# openmv4.net
KiCad netlist of a schematic drawn in Altium Designer
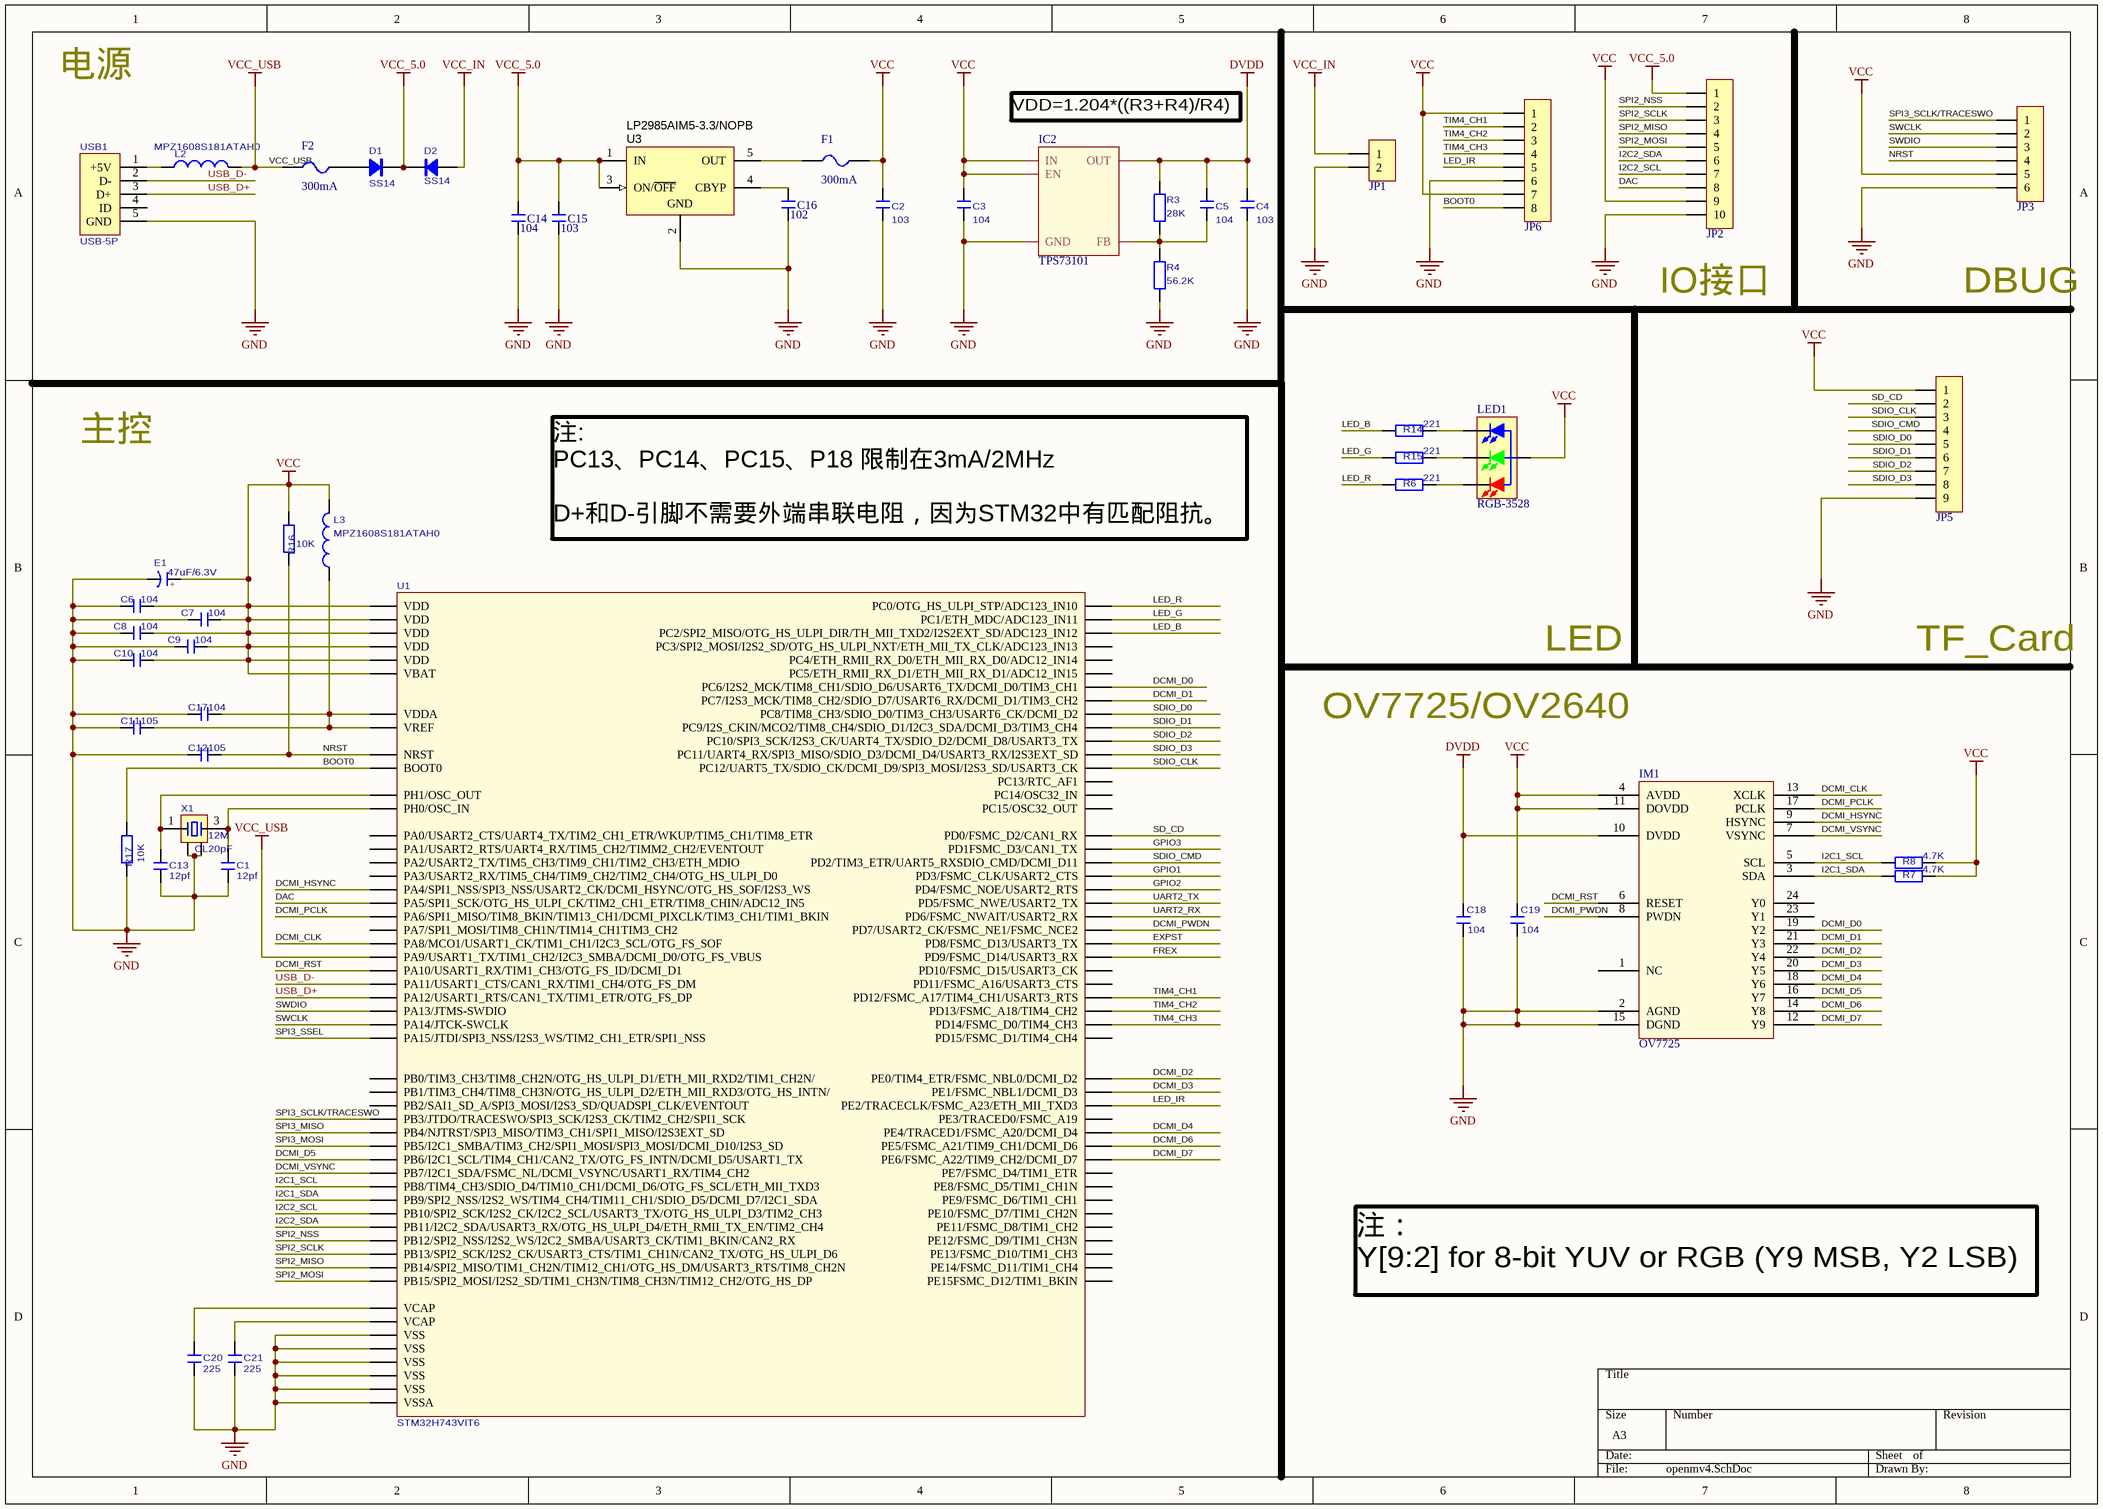
[diagram p0: openmv4.SchDoc]

(export (version "E")
  (design (tool "Eeschema 10.0.6"))
  (components
    (comp (ref "C1")
      (value "12pf")
      (footprint "C 0603_M")
      (description "无极性贴片电容")
      (fields (field (name "版权归属") "源创客"))
      (libsource (lib "3.1   - 电阻-电容-电感") (part "C"))
    )
    (comp (ref "C2")
      (value "103")
      (footprint "C 0603_M")
      (description "无极性贴片电容")
      (fields (field (name "版权归属") "源创客"))
      (libsource (lib "3.1   - 电阻-电容-电感") (part "C"))
    )
    (comp (ref "C3")
      (value "104")
      (footprint "C 0603_M")
      (description "无极性贴片电容")
      (fields (field (name "版权归属") "源创客"))
      (libsource (lib "3.1   - 电阻-电容-电感") (part "C"))
    )
    (comp (ref "C4")
      (value "103")
      (footprint "C 0603_M")
      (description "无极性贴片电容")
      (fields (field (name "版权归属") "源创客"))
      (libsource (lib "3.1   - 电阻-电容-电感") (part "C"))
    )
    (comp (ref "C5")
      (value "104")
      (footprint "C 0603_M")
      (description "无极性贴片电容")
      (fields (field (name "版权归属") "源创客"))
      (libsource (lib "3.1   - 电阻-电容-电感") (part "C"))
    )
    (comp (ref "C6")
      (value "104")
      (footprint "C 0603_M")
      (description "无极性贴片电容")
      (fields (field (name "版权归属") "源创客"))
      (libsource (lib "3.1   - 电阻-电容-电感") (part "C"))
    )
    (comp (ref "C7")
      (value "104")
      (footprint "C 0603_M")
      (description "无极性贴片电容")
      (fields (field (name "版权归属") "源创客"))
      (libsource (lib "3.1   - 电阻-电容-电感") (part "C"))
    )
    (comp (ref "C8")
      (value "104")
      (footprint "C 0603_M")
      (description "无极性贴片电容")
      (fields (field (name "版权归属") "源创客"))
      (libsource (lib "3.1   - 电阻-电容-电感") (part "C"))
    )
    (comp (ref "C9")
      (value "104")
      (footprint "C 0603_M")
      (description "无极性贴片电容")
      (fields (field (name "版权归属") "源创客"))
      (libsource (lib "3.1   - 电阻-电容-电感") (part "C"))
    )
    (comp (ref "C10")
      (value "104")
      (footprint "C 0603_M")
      (description "无极性贴片电容")
      (fields (field (name "版权归属") "源创客"))
      (libsource (lib "3.1   - 电阻-电容-电感") (part "C"))
    )
    (comp (ref "C11")
      (value "105")
      (footprint "C 0603_M")
      (description "无极性贴片电容")
      (fields (field (name "版权归属") "源创客"))
      (libsource (lib "3.1   - 电阻-电容-电感") (part "C"))
    )
    (comp (ref "C12")
      (value "105")
      (footprint "C 0603_M")
      (description "无极性贴片电容")
      (fields (field (name "版权归属") "源创客"))
      (libsource (lib "3.1   - 电阻-电容-电感") (part "C"))
    )
    (comp (ref "C13")
      (value "12pf")
      (footprint "C 0603_M")
      (description "无极性贴片电容")
      (fields (field (name "版权归属") "源创客"))
      (libsource (lib "3.1   - 电阻-电容-电感") (part "C"))
    )
    (comp (ref "C14")
      (value "104")
      (footprint "C 0603_M")
      (description "无极性贴片电容")
      (fields (field (name "版权归属") "源创客"))
      (libsource (lib "3.1   - 电阻-电容-电感") (part "C"))
    )
    (comp (ref "C15")
      (value "103")
      (footprint "C 0603_M")
      (description "无极性贴片电容")
      (fields (field (name "版权归属") "源创客"))
      (libsource (lib "3.1   - 电阻-电容-电感") (part "C"))
    )
    (comp (ref "C16")
      (value "102")
      (footprint "C 0603_M")
      (description "无极性贴片电容")
      (fields (field (name "版权归属") "源创客"))
      (libsource (lib "3.1   - 电阻-电容-电感") (part "C"))
    )
    (comp (ref "C17")
      (value "104")
      (footprint "C 0603_M")
      (description "无极性贴片电容")
      (fields (field (name "版权归属") "源创客"))
      (libsource (lib "3.1   - 电阻-电容-电感") (part "C"))
    )
    (comp (ref "C18")
      (value "104")
      (footprint "C 0603_M")
      (description "无极性贴片电容")
      (fields (field (name "版权归属") "源创客"))
      (libsource (lib "3.1   - 电阻-电容-电感") (part "C"))
    )
    (comp (ref "C19")
      (value "104")
      (footprint "C 0603_M")
      (description "无极性贴片电容")
      (fields (field (name "版权归属") "源创客"))
      (libsource (lib "3.1   - 电阻-电容-电感") (part "C"))
    )
    (comp (ref "C20")
      (value "225")
      (footprint "C 0603_M")
      (description "无极性贴片电容")
      (fields (field (name "版权归属") "源创客"))
      (libsource (lib "3.1   - 电阻-电容-电感") (part "C"))
    )
    (comp (ref "C21")
      (value "225")
      (footprint "C 0603_M")
      (description "无极性贴片电容")
      (fields (field (name "版权归属") "源创客"))
      (libsource (lib "3.1   - 电阻-电容-电感") (part "C"))
    )
    (comp (ref "D1")
      (value "SS14")
      (footprint "SOD-323")
      (description "肖特基二极管")
      (fields (field (name "版权归属") "源创客"))
      (libsource (lib "8.1   - 二极管-整流桥") (part "SS14"))
    )
    (comp (ref "D2")
      (value "SS14")
      (footprint "SOD-323")
      (description "肖特基二极管")
      (fields (field (name "版权归属") "源创客"))
      (libsource (lib "8.1   - 二极管-整流桥") (part "SS14"))
    )
    (comp (ref "E1")
      (value "47uF/6.3V")
      (footprint "CD A(3216)")
      (description "贴片钽电容")
      (fields (field (name "版权归属") "源创客"))
      (libsource (lib "3.1   - 电阻-电容-电感") (part "C-CD"))
    )
    (comp (ref "F1")
      (value "300mA")
      (footprint "FU 0805")
      (description "贴片保险丝")
      (fields (field (name "版权归属") "源创客"))
      (libsource (lib "10.1 - 保险丝-晶振") (part "FU"))
    )
    (comp (ref "F2")
      (value "300mA")
      (footprint "FU 0603")
      (description "贴片保险丝")
      (fields (field (name "版权归属") "源创客"))
      (libsource (lib "10.1 - 保险丝-晶振") (part "FU"))
    )
    (comp (ref "IC2") (value "TPS73101") (footprint "SOT23-5M") (libsource (lib "TPS731") (part "TPS731")))
    (comp (ref "IM1")
      (value "OV7725")
      (footprint "FPC0.5 2H-WS-24P")
      (libsource (lib "OV7725-Down") (part "OV7725_Down"))
    )
    (comp (ref "JP1")
      (value "HDR-1X2")
      (footprint "MX 1.25-WS-2P")
      (description "2P接插件")
      (fields (field (name "版权归属") "源创客"))
      (libsource (lib "4.2   - 接插件-脚距1.25") (part "Header 2"))
    )
    (comp (ref "JP2")
      (value "HDR-1X10")
      (footprint "MX 1.25-WS-10P")
      (description "10P接插件")
      (fields (field (name "版权归属") "源创客"))
      (libsource (lib "4.2   - 接插件-脚距1.25") (part "Header 10"))
    )
    (comp (ref "JP3")
      (value "HDR-1X6")
      (footprint "MX 1.25-WS-6P")
      (description "6P接插件")
      (fields (field (name "版权归属") "源创客"))
      (libsource (lib "4.2   - 接插件-脚距1.25") (part "Header 6"))
    )
    (comp (ref "JP5")
      (value "FPC1.0-9P")
      (footprint "FPC0.5 2H-WS-9P")
      (description "FPC连接器")
      (fields (field (name "版权归属") "源创客"))
      (libsource (lib "4.15 - FPC连接器") (part "FPC-9P"))
    )
    (comp (ref "JP6")
      (value "HDR-1X8")
      (footprint "MX 1.25-WS-8P")
      (description "8P接插件")
      (fields (field (name "版权归属") "源创客"))
      (libsource (lib "4.2   - 接插件-脚距1.25") (part "Header 8"))
    )
    (comp (ref "L2")
      (value "MPZ1608S181ATAH0")
      (footprint "L 0603_M")
      (description "小功率贴片电感")
      (fields (field (name "版权归属") "源创客"))
      (libsource (lib "3.1   - 电阻-电容-电感") (part "L"))
    )
    (comp (ref "L3")
      (value "MPZ1608S181ATAH0")
      (footprint "L 0603_M")
      (description "小功率贴片电感")
      (fields (field (name "版权归属") "源创客"))
      (libsource (lib "3.1   - 电阻-电容-电感") (part "L"))
    )
    (comp (ref "LED1")
      (value "RGB-3528")
      (footprint "LED 3528-4Pin")
      (description "三基色LED")
      (fields (field (name "版权归属") "源创客"))
      (libsource (lib "9.1   - LED") (part "LED-RGB-3528"))
    )
    (comp (ref "R3")
      (value "28K")
      (footprint "R 0603_M")
      (description "贴片电阻")
      (fields (field (name "版权归属") "源创客"))
      (libsource (lib "3.1   - 电阻-电容-电感") (part "R"))
    )
    (comp (ref "R4")
      (value "56.2K")
      (footprint "R 0603_M")
      (description "贴片电阻")
      (fields (field (name "版权归属") "源创客"))
      (libsource (lib "3.1   - 电阻-电容-电感") (part "R"))
    )
    (comp (ref "R6")
      (value "221")
      (footprint "R 0603_M")
      (description "贴片电阻")
      (fields (field (name "版权归属") "源创客"))
      (libsource (lib "3.1   - 电阻-电容-电感") (part "R"))
    )
    (comp (ref "R7")
      (value "4.7K")
      (description "贴片电阻")
      (fields (field (name "版权归属") "源创客"))
      (libsource (lib "3.1   - 电阻-电容-电感") (part "R"))
    )
    (comp (ref "R8")
      (value "4.7K")
      (description "贴片电阻")
      (fields (field (name "版权归属") "源创客"))
      (libsource (lib "3.1   - 电阻-电容-电感") (part "R"))
    )
    (comp (ref "R14")
      (value "221")
      (footprint "R 0603_M")
      (description "贴片电阻")
      (fields (field (name "版权归属") "源创客"))
      (libsource (lib "3.1   - 电阻-电容-电感") (part "R"))
    )
    (comp (ref "R15")
      (value "221")
      (footprint "R 0603_M")
      (description "贴片电阻")
      (fields (field (name "版权归属") "源创客"))
      (libsource (lib "3.1   - 电阻-电容-电感") (part "R"))
    )
    (comp (ref "R16")
      (value "10K")
      (footprint "R 0603_M")
      (description "贴片电阻")
      (fields (field (name "版权归属") "源创客"))
      (libsource (lib "3.1   - 电阻-电容-电感") (part "R"))
    )
    (comp (ref "R17")
      (value "10K")
      (footprint "R 0603_M")
      (description "贴片电阻")
      (fields (field (name "版权归属") "源创客"))
      (libsource (lib "3.1   - 电阻-电容-电感") (part "R"))
    )
    (comp (ref "U1")
      (value "STM32H743VIT6")
      (footprint "LQFP100 14x14_M")
      (libsource (lib "STM32H743VIT6") (part "STM32H743VIT6"))
    )
    (comp (ref "U3")
      (value "LP2985AIM5-3.3/NOPB")
      (footprint "SOT23-5L")
      (description "Micropower 150 mA Low-Noise Ultra Low-Dropout Regulator, 5-pin SOT-23, Pb-Free")
      (fields (field (name "MANUFACTURER") "Texas Instruments") (field (name "PUBLISHER") "Altium Limited"))
      (libsource (lib "NSC LDO") (part "LP2985AIM5-3.3/NOPB"))
    )
    (comp (ref "USB1")
      (value "USB-5P")
      (footprint "USB-MICRO_A")
      (description "微型USB母座")
      (fields (field (name "版权归属") "源创客"))
      (libsource (lib "4.1   - 接口类") (part "USB-5P"))
    )
    (comp (ref "X1")
      (value "12M")
      (footprint "OSC 2025-4P")
      (description "4脚无源晶振")
      (fields (field (name "负载电容") "CL20pF") (field (name "版权归属") "源创客"))
      (libsource (lib "10.1 - 保险丝-晶振") (part "XTAL-4P"))
    )
  )
  (nets
    (net (code "1") (name "/BOOT0") (class "Default")
      (node (ref "JP6") (pin "8") (pinfunction "8_8") (pintype "passive"))
      (node (ref "R17") (pin "2") (pinfunction "2_2") (pintype "passive"))
      (node (ref "U1") (pin "94") (pinfunction "BOOT0_94") (pintype "passive"))
    )
    (net (code "2") (name "/DAC") (class "Default")
      (node (ref "JP2") (pin "8") (pinfunction "8_8") (pintype "passive"))
      (node (ref "U1") (pin "29") (pinfunction "PA5/SPI1_SCK/OTG_HS_ULPI_CK/TIM2_CH1_ETR/TIM8_CHIN/ADC12_IN5_29") (pintype "passive"))
    )
    (net (code "3") (name "/DCMI_CLK") (class "Default")
      (node (ref "IM1") (pin "13") (pinfunction "XCLK_13") (pintype "power_in"))
      (node (ref "U1") (pin "67") (pinfunction "PA8/MCO1/USART1_CK/TIM1_CH1/I2C3_SCL/OTG_FS_SOF_67") (pintype "passive"))
    )
    (net (code "4") (name "/DCMI_D0") (class "Default")
      (node (ref "IM1") (pin "19") (pinfunction "Y2_19") (pintype "power_in"))
      (node (ref "U1") (pin "63") (pinfunction "PC6/I2S2_MCK/TIM8_CH1/SDIO_D6/USART6_TX/DCMI_D0/TIM3_CH1_63") (pintype "passive"))
    )
    (net (code "5") (name "/DCMI_D1") (class "Default")
      (node (ref "IM1") (pin "21") (pinfunction "Y3_21") (pintype "power_in"))
      (node (ref "U1") (pin "64") (pinfunction "PC7/I2S3_MCK/TIM8_CH2/SDIO_D7/USART6_RX/DCMI_D1/TIM3_CH2_64") (pintype "passive"))
    )
    (net (code "6") (name "/DCMI_D2") (class "Default")
      (node (ref "IM1") (pin "22") (pinfunction "Y4_22") (pintype "power_in"))
      (node (ref "U1") (pin "97") (pinfunction "PE0/TIM4_ETR/FSMC_NBL0/DCMI_D2_97") (pintype "passive"))
    )
    (net (code "7") (name "/DCMI_D3") (class "Default")
      (node (ref "IM1") (pin "20") (pinfunction "Y5_20") (pintype "power_in"))
      (node (ref "U1") (pin "98") (pinfunction "PE1/FSMC_NBL1/DCMI_D3_98") (pintype "passive"))
    )
    (net (code "8") (name "/DCMI_D4") (class "Default")
      (node (ref "IM1") (pin "18") (pinfunction "Y6_18") (pintype "power_in"))
      (node (ref "U1") (pin "3") (pinfunction "PE4/TRACED1/FSMC_A20/DCMI_D4_3") (pintype "passive"))
    )
    (net (code "9") (name "/DCMI_D5") (class "Default")
      (node (ref "IM1") (pin "16") (pinfunction "Y7_16") (pintype "power_in"))
      (node (ref "U1") (pin "92") (pinfunction "PB6/I2C1_SCL/TIM4_CH1/CAN2_TX/OTG_FS_INTN/DCMI_D5/USART1_TX_92") (pintype "passive"))
    )
    (net (code "10") (name "/DCMI_D6") (class "Default")
      (node (ref "IM1") (pin "14") (pinfunction "Y8_14") (pintype "power_in"))
      (node (ref "U1") (pin "4") (pinfunction "PE5/FSMC_A21/TIM9_CH1/DCMI_D6_4") (pintype "passive"))
    )
    (net (code "11") (name "/DCMI_D7") (class "Default")
      (node (ref "IM1") (pin "12") (pinfunction "Y9_12") (pintype "power_in"))
      (node (ref "U1") (pin "5") (pinfunction "PE6/FSMC_A22/TIM9_CH2/DCMI_D7_5") (pintype "passive"))
    )
    (net (code "12") (name "/DCMI_HSYNC") (class "Default")
      (node (ref "IM1") (pin "9") (pinfunction "HSYNC_9") (pintype "power_in"))
      (node (ref "U1") (pin "28") (pinfunction "PA4/SPI1_NSS/SPI3_NSS/USART2_CK/DCMI_HSYNC/OTG_HS_SOF/I2S3_WS_28") (pintype "passive"))
    )
    (net (code "13") (name "/DCMI_PCLK") (class "Default")
      (node (ref "IM1") (pin "17") (pinfunction "PCLK_17") (pintype "power_in"))
      (node (ref "U1") (pin "30") (pinfunction "PA6/SPI1_MISO/TIM8_BKIN/TIM13_CH1/DCMI_PIXCLK/TIM3_CH1/TIM1_BKIN_30") (pintype "passive"))
    )
    (net (code "14") (name "/DCMI_PWDN") (class "Default")
      (node (ref "IM1") (pin "8") (pinfunction "PWDN_8") (pintype "power_in"))
      (node (ref "U1") (pin "88") (pinfunction "PD7/USART2_CK/FSMC_NE1/FSMC_NCE2_88") (pintype "passive"))
    )
    (net (code "15") (name "/DCMI_RST") (class "Default")
      (node (ref "IM1") (pin "6") (pinfunction "RESET_6") (pintype "power_in"))
      (node (ref "U1") (pin "69") (pinfunction "PA10/USART1_RX/TIM1_CH3/OTG_FS_ID/DCMI_D1_69") (pintype "passive"))
    )
    (net (code "16") (name "/DCMI_VSYNC") (class "Default")
      (node (ref "IM1") (pin "7") (pinfunction "VSYNC_7") (pintype "power_in"))
      (node (ref "U1") (pin "93") (pinfunction "PB7/I2C1_SDA/FSMC_NL/DCMI_VSYNC/USART1_RX/TIM4_CH2_93") (pintype "passive"))
    )
    (net (code "17") (name "/EXPST") (class "Default")
      (node (ref "U1") (pin "55") (pinfunction "PD8/FSMC_D13/USART3_TX_55") (pintype "passive"))
    )
    (net (code "18") (name "/FREX") (class "Default")
      (node (ref "U1") (pin "56") (pinfunction "PD9/FSMC_D14/USART3_RX_56") (pintype "passive"))
    )
    (net (code "19") (name "/GPIO1") (class "Default")
      (node (ref "U1") (pin "84") (pinfunction "PD3/FSMC_CLK/USART2_CTS_84") (pintype "passive"))
    )
    (net (code "20") (name "/GPIO2") (class "Default")
      (node (ref "U1") (pin "85") (pinfunction "PD4/FSMC_NOE/USART2_RTS_85") (pintype "passive"))
    )
    (net (code "21") (name "/GPIO3") (class "Default")
      (node (ref "U1") (pin "82") (pinfunction "PD1FSMC_D3/CAN1_TX_82") (pintype "passive"))
    )
    (net (code "22") (name "/I2C1_SCL") (class "Default")
      (node (ref "IM1") (pin "5") (pinfunction "SCL_5") (pintype "power_in"))
      (node (ref "R8") (pin "2") (pinfunction "2_2") (pintype "passive"))
      (node (ref "U1") (pin "95") (pinfunction "PB8/TIM4_CH3/SDIO_D4/TIM10_CH1/DCMI_D6/OTG_FS_SCL/ETH_MII_TXD3_95") (pintype "passive"))
    )
    (net (code "23") (name "/I2C1_SDA") (class "Default")
      (node (ref "IM1") (pin "3") (pinfunction "SDA_3") (pintype "power_in"))
      (node (ref "R7") (pin "2") (pinfunction "2_2") (pintype "passive"))
      (node (ref "U1") (pin "96") (pinfunction "PB9/SPI2_NSS/I2S2_WS/TIM4_CH4/TIM11_CH1/SDIO_D5/DCMI_D7/I2C1_SDA_96") (pintype "passive"))
    )
    (net (code "24") (name "/I2C2_SCL") (class "Default")
      (node (ref "JP2") (pin "7") (pinfunction "7_7") (pintype "passive"))
      (node (ref "U1") (pin "46") (pinfunction "PB10/SPI2_SCK/I2S2_CK/I2C2_SCL/USART3_TX/OTG_HS_ULPI_D3/TIM2_CH3_46") (pintype "passive"))
    )
    (net (code "25") (name "/I2C2_SDA") (class "Default")
      (node (ref "JP2") (pin "6") (pinfunction "6_6") (pintype "passive"))
      (node (ref "U1") (pin "47") (pinfunction "PB11/I2C2_SDA/USART3_RX/OTG_HS_ULPI_D4/ETH_RMII_TX_EN/TIM2_CH4_47") (pintype "passive"))
    )
    (net (code "26") (name "/LED_B") (class "Default")
      (node (ref "R14") (pin "2") (pinfunction "2_2") (pintype "passive"))
      (node (ref "U1") (pin "17") (pinfunction "PC2/SPI2_MISO/OTG_HS_ULPI_DIR/TH_MII_TXD2/I2S2EXT_SD/ADC123_IN12_17") (pintype "passive"))
    )
    (net (code "27") (name "/LED_G") (class "Default")
      (node (ref "R15") (pin "2") (pinfunction "2_2") (pintype "passive"))
      (node (ref "U1") (pin "16") (pinfunction "PC1/ETH_MDC/ADC123_IN11_16") (pintype "passive"))
    )
    (net (code "28") (name "/LED_IR") (class "Default")
      (node (ref "JP6") (pin "5") (pinfunction "5_5") (pintype "passive"))
      (node (ref "U1") (pin "1") (pinfunction "PE2/TRACECLK/FSMC_A23/ETH_MII_TXD3_1") (pintype "passive"))
    )
    (net (code "29") (name "/LED_R") (class "Default")
      (node (ref "R6") (pin "2") (pinfunction "2_2") (pintype "passive"))
      (node (ref "U1") (pin "15") (pinfunction "PC0/OTG_HS_ULPI_STP/ADC123_IN10_15") (pintype "passive"))
    )
    (net (code "30") (name "/NRST") (class "Default")
      (node (ref "C12") (pin "1") (pinfunction "1_1") (pintype "passive"))
      (node (ref "JP3") (pin "4") (pinfunction "4_4") (pintype "passive"))
      (node (ref "R16") (pin "1") (pinfunction "1_1") (pintype "passive"))
      (node (ref "U1") (pin "14") (pinfunction "NRST_14") (pintype "passive"))
    )
    (net (code "31") (name "/SDIO_CLK") (class "Default")
      (node (ref "JP5") (pin "3") (pinfunction "3_3") (pintype "passive"))
      (node (ref "U1") (pin "80") (pinfunction "PC12/UART5_TX/SDIO_CK/DCMI_D9/SPI3_MOSI/I2S3_SD/USART3_CK_80") (pintype "passive"))
    )
    (net (code "32") (name "/SDIO_CMD") (class "Default")
      (node (ref "JP5") (pin "4") (pinfunction "4_4") (pintype "passive"))
      (node (ref "U1") (pin "83") (pinfunction "PD2/TIM3_ETR/UART5_RXSDIO_CMD/DCMI_D11_83") (pintype "passive"))
    )
    (net (code "33") (name "/SDIO_D0") (class "Default")
      (node (ref "JP5") (pin "5") (pinfunction "5_5") (pintype "passive"))
      (node (ref "U1") (pin "65") (pinfunction "PC8/TIM8_CH3/SDIO_D0/TIM3_CH3/USART6_CK/DCMI_D2_65") (pintype "passive"))
    )
    (net (code "34") (name "/SDIO_D1") (class "Default")
      (node (ref "JP5") (pin "6") (pinfunction "6_6") (pintype "passive"))
      (node (ref "U1") (pin "66") (pinfunction "PC9/I2S_CKIN/MCO2/TIM8_CH4/SDIO_D1/I2C3_SDA/DCMI_D3/TIM3_CH4_66") (pintype "passive"))
    )
    (net (code "35") (name "/SDIO_D2") (class "Default")
      (node (ref "JP5") (pin "7") (pinfunction "7_7") (pintype "passive"))
      (node (ref "U1") (pin "78") (pinfunction "PC10/SPI3_SCK/I2S3_CK/UART4_TX/SDIO_D2/DCMI_D8/USART3_TX_78") (pintype "passive"))
    )
    (net (code "36") (name "/SDIO_D3") (class "Default")
      (node (ref "JP5") (pin "8") (pinfunction "8_8") (pintype "passive"))
      (node (ref "U1") (pin "79") (pinfunction "PC11/UART4_RX/SPI3_MISO/SDIO_D3/DCMI_D4/USART3_RX/I2S3EXT_SD_79") (pintype "passive"))
    )
    (net (code "37") (name "/SD_CD") (class "Default")
      (node (ref "JP5") (pin "2") (pinfunction "2_2") (pintype "passive"))
      (node (ref "U1") (pin "81") (pinfunction "PD0/FSMC_D2/CAN1_RX_81") (pintype "passive"))
    )
    (net (code "38") (name "/SPI2_MISO") (class "Default")
      (node (ref "JP2") (pin "4") (pinfunction "4_4") (pintype "passive"))
      (node (ref "U1") (pin "53") (pinfunction "PB14/SPI2_MISO/TIM1_CH2N/TIM12_CH1/OTG_HS_DM/USART3_RTS/TIM8_CH2N_53") (pintype "passive"))
    )
    (net (code "39") (name "/SPI2_MOSI") (class "Default")
      (node (ref "JP2") (pin "5") (pinfunction "5_5") (pintype "passive"))
      (node (ref "U1") (pin "54") (pinfunction "PB15/SPI2_MOSI/I2S2_SD/TIM1_CH3N/TIM8_CH3N/TIM12_CH2/OTG_HS_DP_54") (pintype "passive"))
    )
    (net (code "40") (name "/SPI2_NSS") (class "Default")
      (node (ref "JP2") (pin "2") (pinfunction "2_2") (pintype "passive"))
      (node (ref "U1") (pin "51") (pinfunction "PB12/SPI2_NSS/I2S2_WS/I2C2_SMBA/USART3_CK/TIM1_BKIN/CAN2_RX_51") (pintype "passive"))
    )
    (net (code "41") (name "/SPI2_SCLK") (class "Default")
      (node (ref "JP2") (pin "3") (pinfunction "3_3") (pintype "passive"))
      (node (ref "U1") (pin "52") (pinfunction "PB13/SPI2_SCK/I2S2_CK/USART3_CTS/TIM1_CH1N/CAN2_TX/OTG_HS_ULPI_D6_52") (pintype "passive"))
    )
    (net (code "42") (name "/SPI3_MISO") (class "Default")
      (node (ref "U1") (pin "90") (pinfunction "PB4/NJTRST/SPI3_MISO/TIM3_CH1/SPI1_MISO/I2S3EXT_SD_90") (pintype "passive"))
    )
    (net (code "43") (name "/SPI3_MOSI") (class "Default")
      (node (ref "U1") (pin "91") (pinfunction "PB5/I2C1_SMBA/TIM3_CH2/SPI1_MOSI/SPI3_MOSI/DCMI_D10/I2S3_SD_91") (pintype "passive"))
    )
    (net (code "44") (name "/SPI3_SCLK{slash}TRACESWO") (class "Default")
      (node (ref "JP3") (pin "1") (pinfunction "1_1") (pintype "passive"))
      (node (ref "U1") (pin "89") (pinfunction "PB3/JTDO/TRACESWO/SPI3_SCK/I2S3_CK/TIM2_CH2/SPI1_SCK_89") (pintype "passive"))
    )
    (net (code "45") (name "/SPI3_SSEL") (class "Default")
      (node (ref "U1") (pin "77") (pinfunction "PA15/JTDI/SPI3_NSS/I2S3_WS/TIM2_CH1_ETR/SPI1_NSS_77") (pintype "passive"))
    )
    (net (code "46") (name "/SWCLK") (class "Default")
      (node (ref "JP3") (pin "2") (pinfunction "2_2") (pintype "passive"))
      (node (ref "U1") (pin "76") (pinfunction "PA14/JTCK-SWCLK_76") (pintype "passive"))
    )
    (net (code "47") (name "/SWDIO") (class "Default")
      (node (ref "JP3") (pin "3") (pinfunction "3_3") (pintype "passive"))
      (node (ref "U1") (pin "72") (pinfunction "PA13/JTMS-SWDIO_72") (pintype "passive"))
    )
    (net (code "48") (name "/TIM4_CH1") (class "Default")
      (node (ref "JP6") (pin "2") (pinfunction "2_2") (pintype "passive"))
      (node (ref "U1") (pin "59") (pinfunction "PD12/FSMC_A17/TIM4_CH1/USART3_RTS_59") (pintype "passive"))
    )
    (net (code "49") (name "/TIM4_CH2") (class "Default")
      (node (ref "JP6") (pin "3") (pinfunction "3_3") (pintype "passive"))
      (node (ref "U1") (pin "60") (pinfunction "PD13/FSMC_A18/TIM4_CH2_60") (pintype "passive"))
    )
    (net (code "50") (name "/TIM4_CH3") (class "Default")
      (node (ref "JP6") (pin "4") (pinfunction "4_4") (pintype "passive"))
      (node (ref "U1") (pin "61") (pinfunction "PD14/FSMC_D0/TIM4_CH3_61") (pintype "passive"))
    )
    (net (code "51") (name "/UART2_RX") (class "Default")
      (node (ref "U1") (pin "87") (pinfunction "PD6/FSMC_NWAIT/USART2_RX_87") (pintype "passive"))
    )
    (net (code "52") (name "/UART2_TX") (class "Default")
      (node (ref "U1") (pin "86") (pinfunction "PD5/FSMC_NWE/USART2_TX_86") (pintype "passive"))
    )
    (net (code "53") (name "/USB_D+") (class "Default")
      (node (ref "U1") (pin "71") (pinfunction "PA12/USART1_RTS/CAN1_TX/TIM1_ETR/OTG_FS_DP_71") (pintype "passive"))
      (node (ref "USB1") (pin "3") (pinfunction "D+_3") (pintype "passive"))
    )
    (net (code "54") (name "/USB_D-") (class "Default")
      (node (ref "U1") (pin "70") (pinfunction "PA11/USART1_CTS/CAN1_RX/TIM1_CH4/OTG_FS_DM_70") (pintype "passive"))
      (node (ref "USB1") (pin "2") (pinfunction "D-_2") (pintype "passive"))
    )
    (net (code "55") (name "DVDD") (class "Default")
      (node (ref "C18") (pin "2") (pinfunction "2_2") (pintype "passive"))
      (node (ref "C4") (pin "2") (pinfunction "2_2") (pintype "passive"))
      (node (ref "C5") (pin "2") (pinfunction "2_2") (pintype "passive"))
      (node (ref "IC2") (pin "5") (pinfunction "OUT_5") (pintype "passive"))
      (node (ref "IM1") (pin "10") (pinfunction "DVDD_10") (pintype "power_in"))
      (node (ref "R3") (pin "2") (pinfunction "2_2") (pintype "passive"))
    )
    (net (code "56") (name "GND") (class "Default")
      (node (ref "C1") (pin "2") (pinfunction "2_2") (pintype "passive"))
      (node (ref "C10") (pin "2") (pinfunction "2_2") (pintype "passive"))
      (node (ref "C11") (pin "2") (pinfunction "2_2") (pintype "passive"))
      (node (ref "C12") (pin "2") (pinfunction "2_2") (pintype "passive"))
      (node (ref "C13") (pin "2") (pinfunction "2_2") (pintype "passive"))
      (node (ref "C14") (pin "1") (pinfunction "1_1") (pintype "passive"))
      (node (ref "C15") (pin "1") (pinfunction "1_1") (pintype "passive"))
      (node (ref "C16") (pin "1") (pinfunction "1_1") (pintype "passive"))
      (node (ref "C17") (pin "2") (pinfunction "2_2") (pintype "passive"))
      (node (ref "C18") (pin "1") (pinfunction "1_1") (pintype "passive"))
      (node (ref "C19") (pin "1") (pinfunction "1_1") (pintype "passive"))
      (node (ref "C2") (pin "1") (pinfunction "1_1") (pintype "passive"))
      (node (ref "C20") (pin "2") (pinfunction "2_2") (pintype "passive"))
      (node (ref "C21") (pin "2") (pinfunction "2_2") (pintype "passive"))
      (node (ref "C3") (pin "1") (pinfunction "1_1") (pintype "passive"))
      (node (ref "C4") (pin "1") (pinfunction "1_1") (pintype "passive"))
      (node (ref "C6") (pin "2") (pinfunction "2_2") (pintype "passive"))
      (node (ref "C7") (pin "2") (pinfunction "2_2") (pintype "passive"))
      (node (ref "C8") (pin "2") (pinfunction "2_2") (pintype "passive"))
      (node (ref "C9") (pin "2") (pinfunction "2_2") (pintype "passive"))
      (node (ref "E1") (pin "2") (pinfunction "K_2") (pintype "passive"))
      (node (ref "IC2") (pin "2") (pinfunction "GND_2") (pintype "passive"))
      (node (ref "IM1") (pin "15") (pinfunction "DGND_15") (pintype "power_in"))
      (node (ref "IM1") (pin "2") (pinfunction "AGND_2") (pintype "power_in"))
      (node (ref "JP1") (pin "2") (pinfunction "2_2") (pintype "passive"))
      (node (ref "JP2") (pin "10") (pinfunction "10_10") (pintype "passive"))
      (node (ref "JP3") (pin "6") (pinfunction "6_6") (pintype "passive"))
      (node (ref "JP5") (pin "9") (pinfunction "9_9") (pintype "passive"))
      (node (ref "JP6") (pin "6") (pinfunction "6_6") (pintype "passive"))
      (node (ref "R17") (pin "1") (pinfunction "1_1") (pintype "passive"))
      (node (ref "R4") (pin "1") (pinfunction "1_1") (pintype "passive"))
      (node (ref "U1") (pin "10") (pinfunction "VSS_10") (pintype "passive"))
      (node (ref "U1") (pin "19") (pinfunction "VSSA_19") (pintype "passive"))
      (node (ref "U1") (pin "26") (pinfunction "VSS_26") (pintype "passive"))
      (node (ref "U1") (pin "49") (pinfunction "VSS_49") (pintype "passive"))
      (node (ref "U1") (pin "74") (pinfunction "VSS_74") (pintype "passive"))
      (node (ref "U1") (pin "99") (pinfunction "VSS_99") (pintype "passive"))
      (node (ref "U3") (pin "2") (pinfunction "GND_2") (pintype "power_in"))
      (node (ref "USB1") (pin "5") (pinfunction "GND_5") (pintype "passive"))
      (node (ref "X1") (pin "2") (pinfunction "2_2") (pintype "passive"))
      (node (ref "X1") (pin "4") (pinfunction "4_4") (pintype "passive"))
    )
    (net (code "57") (name "Net-(C20-Pad1)") (class "Default")
      (node (ref "C20") (pin "1") (pinfunction "1_1") (pintype "passive"))
      (node (ref "U1") (pin "48") (pinfunction "VCAP_48") (pintype "passive"))
    )
    (net (code "58") (name "Net-(C21-Pad1)") (class "Default")
      (node (ref "C21") (pin "1") (pinfunction "1_1") (pintype "passive"))
      (node (ref "U1") (pin "73") (pinfunction "VCAP_73") (pintype "passive"))
    )
    (net (code "59") (name "Net-(D1-A)") (class "Default")
      (node (ref "D1") (pin "1") (pinfunction "A_1") (pintype "passive"))
      (node (ref "F2") (pin "1") (pinfunction "1_1") (pintype "passive"))
    )
    (net (code "60") (name "Net-(IC2-FB)") (class "Default")
      (node (ref "C5") (pin "1") (pinfunction "1_1") (pintype "passive"))
      (node (ref "IC2") (pin "4") (pinfunction "FB_4") (pintype "passive"))
      (node (ref "R3") (pin "1") (pinfunction "1_1") (pintype "passive"))
      (node (ref "R4") (pin "2") (pinfunction "2_2") (pintype "passive"))
    )
    (net (code "61") (name "Net-(LED1-BULE_K)") (class "Default")
      (node (ref "LED1") (pin "3") (pinfunction "BULE_K_3") (pintype "passive"))
      (node (ref "R14") (pin "1") (pinfunction "1_1") (pintype "passive"))
    )
    (net (code "62") (name "Net-(LED1-GREEN_K)") (class "Default")
      (node (ref "LED1") (pin "2") (pinfunction "GREEN_K_2") (pintype "passive"))
      (node (ref "R15") (pin "1") (pinfunction "1_1") (pintype "passive"))
    )
    (net (code "63") (name "Net-(LED1-RED_K)") (class "Default")
      (node (ref "LED1") (pin "1") (pinfunction "RED_K_1") (pintype "passive"))
      (node (ref "R6") (pin "1") (pinfunction "1_1") (pintype "passive"))
    )
    (net (code "64") (name "Net-(U1-PH0{slash}OSC_IN)") (class "Default")
      (node (ref "C1") (pin "1") (pinfunction "1_1") (pintype "passive"))
      (node (ref "U1") (pin "12") (pinfunction "PH0/OSC_IN_12") (pintype "passive"))
      (node (ref "X1") (pin "3") (pinfunction "3_3") (pintype "passive"))
    )
    (net (code "65") (name "Net-(U1-PH1{slash}OSC_OUT)") (class "Default")
      (node (ref "C13") (pin "1") (pinfunction "1_1") (pintype "passive"))
      (node (ref "U1") (pin "13") (pinfunction "PH1/OSC_OUT_13") (pintype "passive"))
      (node (ref "X1") (pin "1") (pinfunction "1_1") (pintype "passive"))
    )
    (net (code "66") (name "Net-(U1-VDDA)") (class "Default")
      (node (ref "C11") (pin "1") (pinfunction "1_1") (pintype "passive"))
      (node (ref "C17") (pin "1") (pinfunction "1_1") (pintype "passive"))
      (node (ref "L3") (pin "1") (pinfunction "1_1") (pintype "passive"))
      (node (ref "U1") (pin "20") (pinfunction "VREF_20") (pintype "passive"))
      (node (ref "U1") (pin "21") (pinfunction "VDDA_21") (pintype "passive"))
    )
    (net (code "67") (name "Net-(U3-CBYP)") (class "Default")
      (node (ref "C16") (pin "2") (pinfunction "2_2") (pintype "passive"))
      (node (ref "U3") (pin "4") (pinfunction "CBYP_4") (pintype "passive"))
    )
    (net (code "68") (name "Net-(U3-OUT)") (class "Default")
      (node (ref "F1") (pin "2") (pinfunction "2_2") (pintype "passive"))
      (node (ref "U3") (pin "5") (pinfunction "OUT_5") (pintype "power_in"))
    )
    (net (code "69") (name "Net-(USB1-+5V)") (class "Default")
      (node (ref "L2") (pin "1") (pinfunction "1_1") (pintype "passive"))
      (node (ref "USB1") (pin "1") (pinfunction "+5V_1") (pintype "passive"))
    )
    (net (code "70") (name "VCC") (class "Default")
      (node (ref "C10") (pin "1") (pinfunction "1_1") (pintype "passive"))
      (node (ref "C19") (pin "2") (pinfunction "2_2") (pintype "passive"))
      (node (ref "C2") (pin "2") (pinfunction "2_2") (pintype "passive"))
      (node (ref "C3") (pin "2") (pinfunction "2_2") (pintype "passive"))
      (node (ref "C6") (pin "1") (pinfunction "1_1") (pintype "passive"))
      (node (ref "C7") (pin "1") (pinfunction "1_1") (pintype "passive"))
      (node (ref "C8") (pin "1") (pinfunction "1_1") (pintype "passive"))
      (node (ref "C9") (pin "1") (pinfunction "1_1") (pintype "passive"))
      (node (ref "E1") (pin "1") (pinfunction "A_1") (pintype "passive"))
      (node (ref "F1") (pin "1") (pinfunction "1_1") (pintype "passive"))
      (node (ref "IC2") (pin "1") (pinfunction "IN_1") (pintype "passive"))
      (node (ref "IC2") (pin "3") (pinfunction "EN_3") (pintype "passive"))
      (node (ref "IM1") (pin "11") (pinfunction "DOVDD_11") (pintype "power_in"))
      (node (ref "IM1") (pin "4") (pinfunction "AVDD_4") (pintype "power_in"))
      (node (ref "JP2") (pin "9") (pinfunction "9_9") (pintype "passive"))
      (node (ref "JP3") (pin "5") (pinfunction "5_5") (pintype "passive"))
      (node (ref "JP5") (pin "1") (pinfunction "1_1") (pintype "passive"))
      (node (ref "JP6") (pin "1") (pinfunction "1_1") (pintype "passive"))
      (node (ref "JP6") (pin "7") (pinfunction "7_7") (pintype "passive"))
      (node (ref "L3") (pin "2") (pinfunction "2_2") (pintype "passive"))
      (node (ref "LED1") (pin "4") (pinfunction "A_4") (pintype "passive"))
      (node (ref "R16") (pin "2") (pinfunction "2_2") (pintype "passive"))
      (node (ref "R7") (pin "1") (pinfunction "1_1") (pintype "passive"))
      (node (ref "R8") (pin "1") (pinfunction "1_1") (pintype "passive"))
      (node (ref "U1") (pin "100") (pinfunction "VDD_100") (pintype "passive"))
      (node (ref "U1") (pin "11") (pinfunction "VDD_11") (pintype "passive"))
      (node (ref "U1") (pin "27") (pinfunction "VDD_27") (pintype "passive"))
      (node (ref "U1") (pin "50") (pinfunction "VDD_50") (pintype "passive"))
      (node (ref "U1") (pin "6") (pinfunction "VBAT_6") (pintype "passive"))
      (node (ref "U1") (pin "75") (pinfunction "VDD_75") (pintype "passive"))
    )
    (net (code "71") (name "VCC_5.0") (class "Default")
      (node (ref "C14") (pin "2") (pinfunction "2_2") (pintype "passive"))
      (node (ref "C15") (pin "2") (pinfunction "2_2") (pintype "passive"))
      (node (ref "D1") (pin "2") (pinfunction "K_2") (pintype "passive"))
      (node (ref "D2") (pin "2") (pinfunction "K_2") (pintype "passive"))
      (node (ref "JP2") (pin "1") (pinfunction "1_1") (pintype "passive"))
      (node (ref "U3") (pin "1") (pinfunction "IN_1") (pintype "power_in"))
      (node (ref "U3") (pin "3") (pinfunction "ON/~{OFF}_3") (pintype "input"))
    )
    (net (code "72") (name "VCC_IN") (class "Default")
      (node (ref "D2") (pin "1") (pinfunction "A_1") (pintype "passive"))
      (node (ref "JP1") (pin "1") (pinfunction "1_1") (pintype "passive"))
    )
    (net (code "73") (name "VCC_USB") (class "Default")
      (node (ref "F2") (pin "2") (pinfunction "2_2") (pintype "passive"))
      (node (ref "L2") (pin "2") (pinfunction "2_2") (pintype "passive"))
      (node (ref "U1") (pin "68") (pinfunction "PA9/USART1_TX/TIM1_CH2/I2C3_SMBA/DCMI_D0/OTG_FS_VBUS_68") (pintype "passive"))
    )
    (net (code "74") (name "unconnected-(IM1-NC-Pad1)") (class "Default")
      (node (ref "IM1") (pin "1") (pinfunction "NC_1") (pintype "power_in"))
    )
    (net (code "75") (name "unconnected-(IM1-Y0-Pad24)") (class "Default")
      (node (ref "IM1") (pin "24") (pinfunction "Y0_24") (pintype "power_in"))
    )
    (net (code "76") (name "unconnected-(IM1-Y1-Pad23)") (class "Default")
      (node (ref "IM1") (pin "23") (pinfunction "Y1_23") (pintype "power_in"))
    )
    (net (code "77") (name "unconnected-(U1-PA0{slash}USART2_CTS{slash}UART4_TX{slash}TIM2_CH1_ETR{slash}WKUP{slash}TIM5_CH1{slash}TIM8_ETR-Pad22)") (class "Default")
      (node (ref "U1") (pin "22") (pinfunction "PA0/USART2_CTS/UART4_TX/TIM2_CH1_ETR/WKUP/TIM5_CH1/TIM8_ETR_22") (pintype "passive"))
    )
    (net (code "78") (name "unconnected-(U1-PA1{slash}USART2_RTS{slash}UART4_RX{slash}TIM5_CH2{slash}TIMM2_CH2{slash}EVENTOUT-Pad23)") (class "Default")
      (node (ref "U1") (pin "23") (pinfunction "PA1/USART2_RTS/UART4_RX/TIM5_CH2/TIMM2_CH2/EVENTOUT_23") (pintype "passive"))
    )
    (net (code "79") (name "unconnected-(U1-PA2{slash}USART2_TX{slash}TIM5_CH3{slash}TIM9_CH1{slash}TIM2_CH3{slash}ETH_MDIO-Pad24)") (class "Default")
      (node (ref "U1") (pin "24") (pinfunction "PA2/USART2_TX/TIM5_CH3/TIM9_CH1/TIM2_CH3/ETH_MDIO_24") (pintype "passive"))
    )
    (net (code "80") (name "unconnected-(U1-PA3{slash}USART2_RX{slash}TIM5_CH4{slash}TIM9_CH2{slash}TIM2_CH4{slash}OTG_HS_ULPI_D0-Pad25)") (class "Default")
      (node (ref "U1") (pin "25") (pinfunction "PA3/USART2_RX/TIM5_CH4/TIM9_CH2/TIM2_CH4/OTG_HS_ULPI_D0_25") (pintype "passive"))
    )
    (net (code "81") (name "unconnected-(U1-PA7{slash}SPI1_MOSI{slash}TIM8_CH1N{slash}TIM14_CH1TIM3_CH2-Pad31)") (class "Default")
      (node (ref "U1") (pin "31") (pinfunction "PA7/SPI1_MOSI/TIM8_CH1N/TIM14_CH1TIM3_CH2_31") (pintype "passive"))
    )
    (net (code "82") (name "unconnected-(U1-PB0{slash}TIM3_CH3{slash}TIM8_CH2N{slash}OTG_HS_ULPI_D1{slash}ETH_MII_RXD2{slash}TIM1_CH2N{slash}-Pad34)") (class "Default")
      (node (ref "U1") (pin "34") (pinfunction "PB0/TIM3_CH3/TIM8_CH2N/OTG_HS_ULPI_D1/ETH_MII_RXD2/TIM1_CH2N/_34") (pintype "passive"))
    )
    (net (code "83") (name "unconnected-(U1-PB1{slash}TIM3_CH4{slash}TIM8_CH3N{slash}OTG_HS_ULPI_D2{slash}ETH_MII_RXD3{slash}OTG_HS_INTN{slash}-Pad35)") (class "Default")
      (node (ref "U1") (pin "35") (pinfunction "PB1/TIM3_CH4/TIM8_CH3N/OTG_HS_ULPI_D2/ETH_MII_RXD3/OTG_HS_INTN/_35") (pintype "passive"))
    )
    (net (code "84") (name "unconnected-(U1-PB2{slash}SAI1_SD_A{slash}SPI3_MOSI{slash}I2S3_SD{slash}QUADSPI_CLK{slash}EVENTOUT-Pad36)") (class "Default")
      (node (ref "U1") (pin "36") (pinfunction "PB2/SAI1_SD_A/SPI3_MOSI/I2S3_SD/QUADSPI_CLK/EVENTOUT_36") (pintype "passive"))
    )
    (net (code "85") (name "unconnected-(U1-PC3{slash}SPI2_MOSI{slash}I2S2_SD{slash}OTG_HS_ULPI_NXT{slash}ETH_MII_TX_CLK{slash}ADC123_IN13-Pad18)") (class "Default")
      (node (ref "U1") (pin "18") (pinfunction "PC3/SPI2_MOSI/I2S2_SD/OTG_HS_ULPI_NXT/ETH_MII_TX_CLK/ADC123_IN13_18") (pintype "passive"))
    )
    (net (code "86") (name "unconnected-(U1-PC4{slash}ETH_RMII_RX_D0{slash}ETH_MII_RX_D0{slash}ADC12_IN14-Pad32)") (class "Default")
      (node (ref "U1") (pin "32") (pinfunction "PC4/ETH_RMII_RX_D0/ETH_MII_RX_D0/ADC12_IN14_32") (pintype "passive"))
    )
    (net (code "87") (name "unconnected-(U1-PC5{slash}ETH_RMII_RX_D1{slash}ETH_MII_RX_D1{slash}ADC12_IN15-Pad33)") (class "Default")
      (node (ref "U1") (pin "33") (pinfunction "PC5/ETH_RMII_RX_D1/ETH_MII_RX_D1/ADC12_IN15_33") (pintype "passive"))
    )
    (net (code "88") (name "unconnected-(U1-PC13{slash}RTC_AF1-Pad7)") (class "Default")
      (node (ref "U1") (pin "7") (pinfunction "PC13/RTC_AF1_7") (pintype "passive"))
    )
    (net (code "89") (name "unconnected-(U1-PC14{slash}OSC32_IN-Pad8)") (class "Default")
      (node (ref "U1") (pin "8") (pinfunction "PC14/OSC32_IN_8") (pintype "passive"))
    )
    (net (code "90") (name "unconnected-(U1-PC15{slash}OSC32_OUT-Pad9)") (class "Default")
      (node (ref "U1") (pin "9") (pinfunction "PC15/OSC32_OUT_9") (pintype "passive"))
    )
    (net (code "91") (name "unconnected-(U1-PD10{slash}FSMC_D15{slash}USART3_CK-Pad57)") (class "Default")
      (node (ref "U1") (pin "57") (pinfunction "PD10/FSMC_D15/USART3_CK_57") (pintype "passive"))
    )
    (net (code "92") (name "unconnected-(U1-PD11{slash}FSMC_A16{slash}USART3_CTS-Pad58)") (class "Default")
      (node (ref "U1") (pin "58") (pinfunction "PD11/FSMC_A16/USART3_CTS_58") (pintype "passive"))
    )
    (net (code "93") (name "unconnected-(U1-PD15{slash}FSMC_D1{slash}TIM4_CH4-Pad62)") (class "Default")
      (node (ref "U1") (pin "62") (pinfunction "PD15/FSMC_D1/TIM4_CH4_62") (pintype "passive"))
    )
    (net (code "94") (name "unconnected-(U1-PE3{slash}TRACED0{slash}FSMC_A19-Pad2)") (class "Default")
      (node (ref "U1") (pin "2") (pinfunction "PE3/TRACED0/FSMC_A19_2") (pintype "passive"))
    )
    (net (code "95") (name "unconnected-(U1-PE7{slash}FSMC_D4{slash}TIM1_ETR-Pad37)") (class "Default")
      (node (ref "U1") (pin "37") (pinfunction "PE7/FSMC_D4/TIM1_ETR_37") (pintype "passive"))
    )
    (net (code "96") (name "unconnected-(U1-PE8{slash}FSMC_D5{slash}TIM1_CH1N-Pad38)") (class "Default")
      (node (ref "U1") (pin "38") (pinfunction "PE8/FSMC_D5/TIM1_CH1N_38") (pintype "passive"))
    )
    (net (code "97") (name "unconnected-(U1-PE9{slash}FSMC_D6{slash}TIM1_CH1-Pad39)") (class "Default")
      (node (ref "U1") (pin "39") (pinfunction "PE9/FSMC_D6/TIM1_CH1_39") (pintype "passive"))
    )
    (net (code "98") (name "unconnected-(U1-PE10{slash}FSMC_D7{slash}TIM1_CH2N-Pad40)") (class "Default")
      (node (ref "U1") (pin "40") (pinfunction "PE10/FSMC_D7/TIM1_CH2N_40") (pintype "passive"))
    )
    (net (code "99") (name "unconnected-(U1-PE11{slash}FSMC_D8{slash}TIM1_CH2-Pad41)") (class "Default")
      (node (ref "U1") (pin "41") (pinfunction "PE11/FSMC_D8/TIM1_CH2_41") (pintype "passive"))
    )
    (net (code "100") (name "unconnected-(U1-PE12{slash}FSMC_D9{slash}TIM1_CH3N-Pad42)") (class "Default")
      (node (ref "U1") (pin "42") (pinfunction "PE12/FSMC_D9/TIM1_CH3N_42") (pintype "passive"))
    )
    (net (code "101") (name "unconnected-(U1-PE13{slash}FSMC_D10{slash}TIM1_CH3-Pad43)") (class "Default")
      (node (ref "U1") (pin "43") (pinfunction "PE13/FSMC_D10/TIM1_CH3_43") (pintype "passive"))
    )
    (net (code "102") (name "unconnected-(U1-PE14{slash}FSMC_D11{slash}TIM1_CH4-Pad44)") (class "Default")
      (node (ref "U1") (pin "44") (pinfunction "PE14/FSMC_D11/TIM1_CH4_44") (pintype "passive"))
    )
    (net (code "103") (name "unconnected-(U1-PE15FSMC_D12{slash}TIM1_BKIN-Pad45)") (class "Default")
      (node (ref "U1") (pin "45") (pinfunction "PE15FSMC_D12/TIM1_BKIN_45") (pintype "passive"))
    )
    (net (code "104") (name "unconnected-(USB1-ID-Pad4)") (class "Default")
      (node (ref "USB1") (pin "4") (pinfunction "ID_4") (pintype "passive"))
    )
  )
)
